# snesslot.net
KiCad netlist of a schematic drawn in Altium Designer
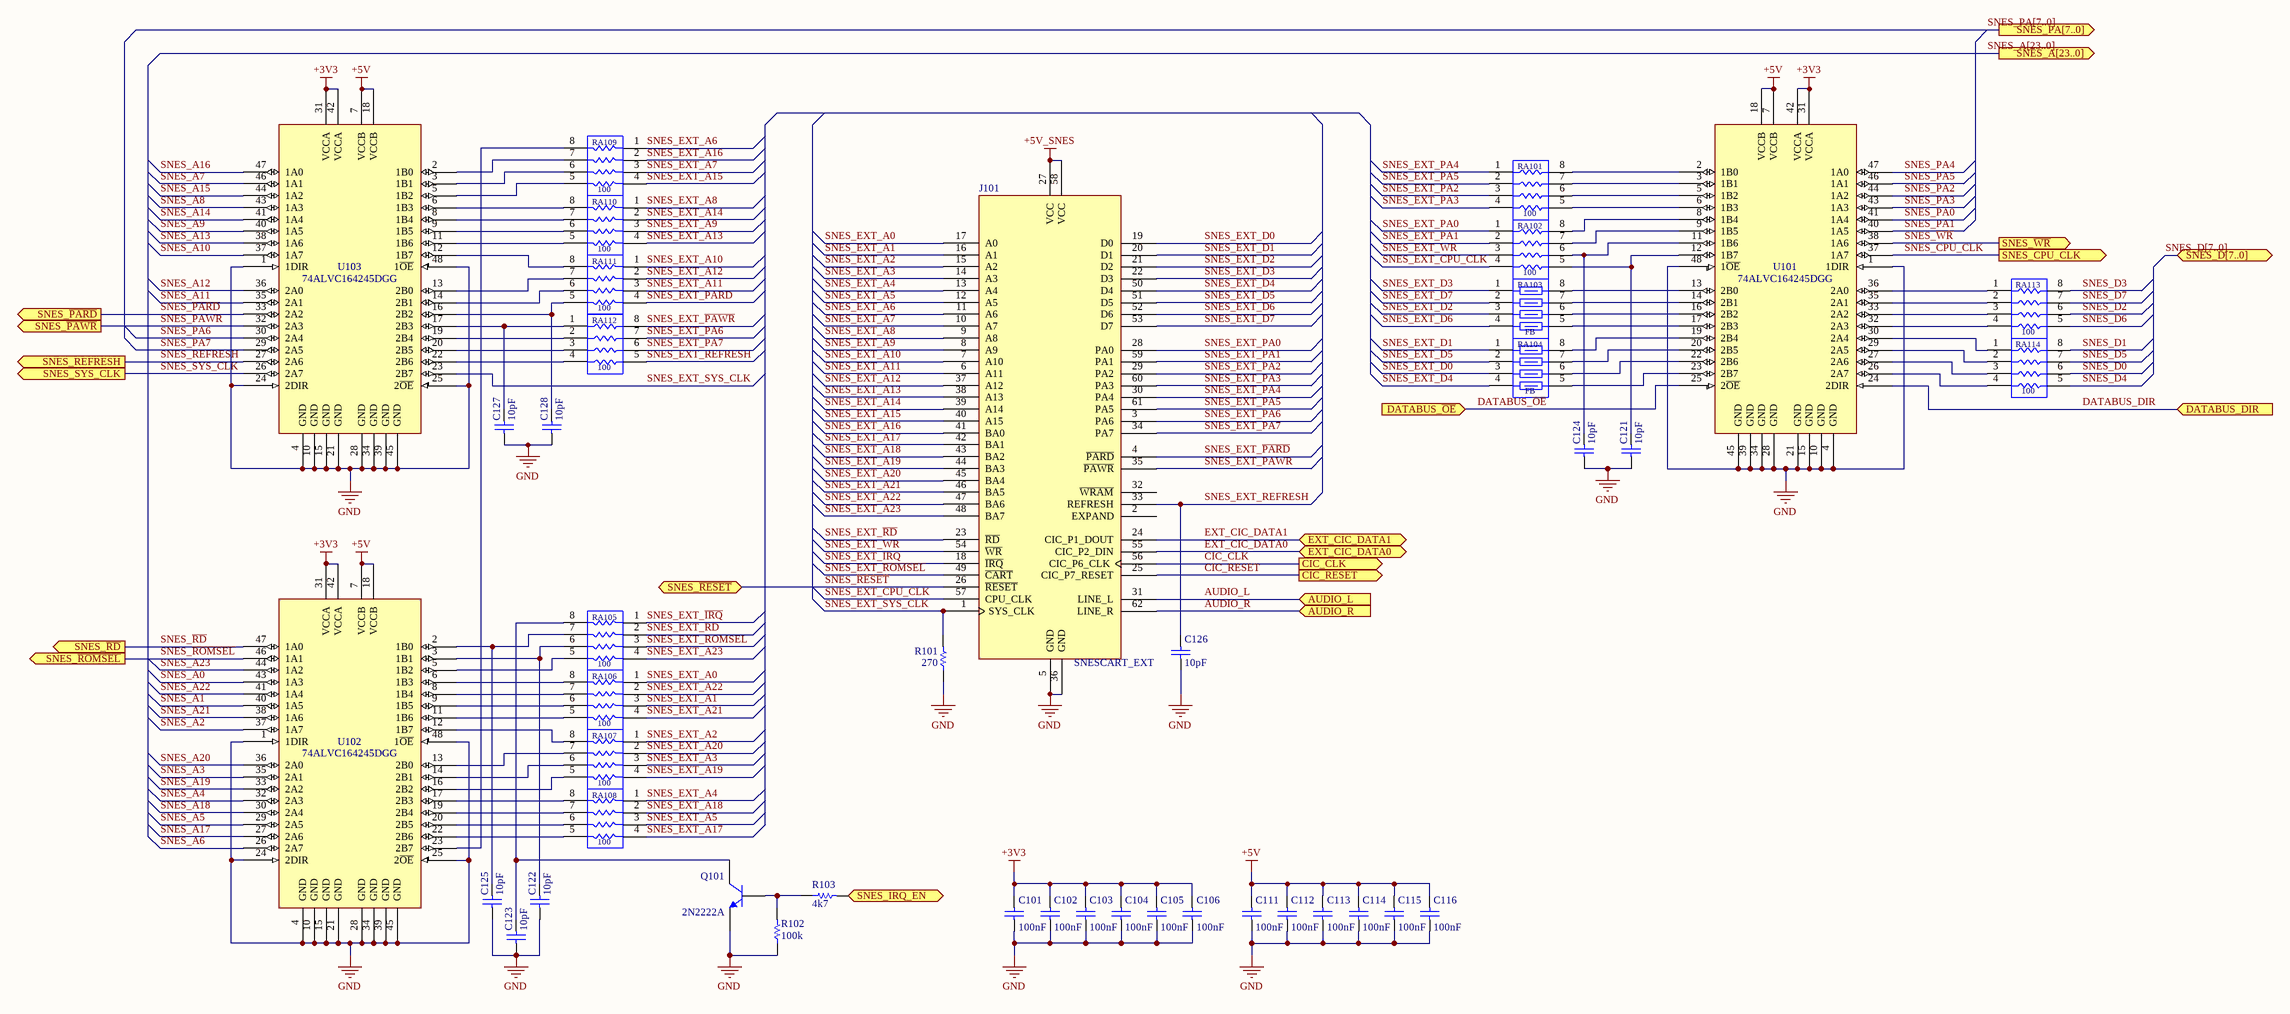
[diagram p0: snesslot.SchDoc]

(export (version "E")
  (design (tool "Eeschema 10.0.6"))
  (components
    (comp (ref "C101")
      (value "100nF")
      (footprint "SM0805")
      (description "Capacitor")
      (libsource (lib "Miscellaneous Devices") (part "Cap"))
    )
    (comp (ref "C102")
      (value "100nF")
      (footprint "SM0805")
      (description "Capacitor")
      (libsource (lib "Miscellaneous Devices") (part "Cap"))
    )
    (comp (ref "C103")
      (value "100nF")
      (footprint "SM0805")
      (description "Capacitor")
      (libsource (lib "Miscellaneous Devices") (part "Cap"))
    )
    (comp (ref "C104")
      (value "100nF")
      (footprint "SM0805")
      (description "Capacitor")
      (libsource (lib "Miscellaneous Devices") (part "Cap"))
    )
    (comp (ref "C105")
      (value "100nF")
      (footprint "SM0805")
      (description "Capacitor")
      (libsource (lib "Miscellaneous Devices") (part "Cap"))
    )
    (comp (ref "C106")
      (value "100nF")
      (footprint "SM0805")
      (description "Capacitor")
      (libsource (lib "Miscellaneous Devices") (part "Cap"))
    )
    (comp (ref "C111")
      (value "100nF")
      (footprint "SM0805")
      (description "Capacitor")
      (libsource (lib "Miscellaneous Devices") (part "Cap"))
    )
    (comp (ref "C112")
      (value "100nF")
      (footprint "SM0805")
      (description "Capacitor")
      (libsource (lib "Miscellaneous Devices") (part "Cap"))
    )
    (comp (ref "C113")
      (value "100nF")
      (footprint "SM0805")
      (description "Capacitor")
      (libsource (lib "Miscellaneous Devices") (part "Cap"))
    )
    (comp (ref "C114")
      (value "100nF")
      (footprint "SM0805")
      (description "Capacitor")
      (libsource (lib "Miscellaneous Devices") (part "Cap"))
    )
    (comp (ref "C115")
      (value "100nF")
      (footprint "SM0805")
      (description "Capacitor")
      (libsource (lib "Miscellaneous Devices") (part "Cap"))
    )
    (comp (ref "C116")
      (value "100nF")
      (footprint "SM0805")
      (description "Capacitor")
      (libsource (lib "Miscellaneous Devices") (part "Cap"))
    )
    (comp (ref "C121")
      (value "10pF")
      (footprint "SM0805")
      (description "Capacitor")
      (libsource (lib "Miscellaneous Devices") (part "Cap"))
    )
    (comp (ref "C122")
      (value "10pF")
      (footprint "SM0805")
      (description "Capacitor")
      (libsource (lib "Miscellaneous Devices") (part "Cap"))
    )
    (comp (ref "C123")
      (value "10pF")
      (footprint "SM0805")
      (description "Capacitor")
      (libsource (lib "Miscellaneous Devices") (part "Cap"))
    )
    (comp (ref "C124")
      (value "10pF")
      (footprint "SM0805")
      (description "Capacitor")
      (libsource (lib "Miscellaneous Devices") (part "Cap"))
    )
    (comp (ref "C125")
      (value "10pF")
      (footprint "SM0805")
      (description "Capacitor")
      (libsource (lib "Miscellaneous Devices") (part "Cap"))
    )
    (comp (ref "C126")
      (value "10pF")
      (footprint "SM0805")
      (description "Capacitor")
      (libsource (lib "Miscellaneous Devices") (part "Cap"))
    )
    (comp (ref "C127")
      (value "10pF")
      (footprint "SM0805")
      (description "Capacitor")
      (libsource (lib "Miscellaneous Devices") (part "Cap"))
    )
    (comp (ref "C128")
      (value "10pF")
      (footprint "SM0805")
      (description "Capacitor")
      (libsource (lib "Miscellaneous Devices") (part "Cap"))
    )
    (comp (ref "J101")
      (value "SNESCART_EXT")
      (footprint "SNESCART_EDGE_CONN")
      (libsource (lib "Schlib1") (part "SNESCART_EXT"))
    )
    (comp (ref "Q101")
      (value "2N2222A")
      (footprint "SOT23EBC")
      (description "NPN Transistor")
      (libsource (lib "Schlib1") (part "NPN"))
    )
    (comp (ref "R101")
      (value "270")
      (footprint "SM0805")
      (description "Resistor")
      (libsource (lib "Miscellaneous Devices") (part "Res1"))
    )
    (comp (ref "R102")
      (value "100k")
      (footprint "SM0805")
      (description "Resistor")
      (libsource (lib "Miscellaneous Devices") (part "Res1"))
    )
    (comp (ref "R103")
      (value "4k7")
      (footprint "SM0805")
      (description "Resistor")
      (libsource (lib "Miscellaneous Devices") (part "Res1"))
    )
    (comp (ref "RA101")
      (value "100")
      (footprint "R_PACK_1206_2")
      (description "Four Resistor Array")
      (libsource (lib "Schlib1") (part "R_PACK4"))
    )
    (comp (ref "RA102")
      (value "100")
      (footprint "R_PACK_1206_2")
      (description "Four Resistor Array")
      (libsource (lib "Schlib1") (part "R_PACK4"))
    )
    (comp (ref "RA103")
      (value "FB")
      (footprint "R_PACK_1206_2")
      (description "Four Ferrite Bead Array")
      (libsource (lib "Schlib1") (part "FB_PACK4"))
    )
    (comp (ref "RA104")
      (value "FB")
      (footprint "R_PACK_1206_2")
      (description "Four Ferrite Bead Array")
      (libsource (lib "Schlib1") (part "FB_PACK4"))
    )
    (comp (ref "RA105")
      (value "100")
      (footprint "R_PACK_1206_2")
      (description "Four Resistor Array")
      (libsource (lib "Schlib1") (part "R_PACK4"))
    )
    (comp (ref "RA106")
      (value "100")
      (footprint "R_PACK_1206_2")
      (description "Four Resistor Array")
      (libsource (lib "Schlib1") (part "R_PACK4"))
    )
    (comp (ref "RA107")
      (value "100")
      (footprint "R_PACK_1206_2")
      (description "Four Resistor Array")
      (libsource (lib "Schlib1") (part "R_PACK4"))
    )
    (comp (ref "RA108")
      (value "100")
      (footprint "R_PACK_1206_2")
      (description "Four Resistor Array")
      (libsource (lib "Schlib1") (part "R_PACK4"))
    )
    (comp (ref "RA109")
      (value "100")
      (footprint "R_PACK_1206_2")
      (description "Four Resistor Array")
      (libsource (lib "Schlib1") (part "R_PACK4"))
    )
    (comp (ref "RA110")
      (value "100")
      (footprint "R_PACK_1206_2")
      (description "Four Resistor Array")
      (libsource (lib "Schlib1") (part "R_PACK4"))
    )
    (comp (ref "RA111")
      (value "100")
      (footprint "R_PACK_1206_2")
      (description "Four Resistor Array")
      (libsource (lib "Schlib1") (part "R_PACK4"))
    )
    (comp (ref "RA112")
      (value "100")
      (footprint "R_PACK_1206_2")
      (description "Four Resistor Array")
      (libsource (lib "Schlib1") (part "R_PACK4"))
    )
    (comp (ref "RA113")
      (value "100")
      (footprint "R_PACK_1206_2")
      (description "Four Resistor Array")
      (libsource (lib "Schlib1") (part "R_PACK4"))
    )
    (comp (ref "RA114")
      (value "100")
      (footprint "R_PACK_1206_2")
      (description "Four Resistor Array")
      (libsource (lib "Schlib1") (part "R_PACK4"))
    )
    (comp (ref "U101")
      (value "74ALVC164245DGG")
      (footprint "TSSOP48")
      (libsource (lib "") (part "74ALVC164245_1"))
    )
    (comp (ref "U102")
      (value "74ALVC164245DGG")
      (footprint "TSSOP48")
      (libsource (lib "Schlib1") (part "74ALVC164245"))
    )
    (comp (ref "U103")
      (value "74ALVC164245DGG")
      (footprint "TSSOP48")
      (libsource (lib "Schlib1") (part "74ALVC164245"))
    )
  )
  (nets
    (net (code "1") (name "+3V3") (class "Default")
      (node (ref "C101") (pin "2") (pinfunction "2_2") (pintype "passive"))
      (node (ref "C102") (pin "2") (pinfunction "2_2") (pintype "passive"))
      (node (ref "C103") (pin "2") (pinfunction "2_2") (pintype "passive"))
      (node (ref "C104") (pin "2") (pinfunction "2_2") (pintype "passive"))
      (node (ref "C105") (pin "2") (pinfunction "2_2") (pintype "passive"))
      (node (ref "C106") (pin "2") (pinfunction "2_2") (pintype "passive"))
      (node (ref "U101") (pin "31") (pinfunction "VCCA_31") (pintype "power_in"))
      (node (ref "U101") (pin "42") (pinfunction "VCCA_42") (pintype "power_in"))
      (node (ref "U102") (pin "31") (pinfunction "VCCA_31") (pintype "power_in"))
      (node (ref "U102") (pin "42") (pinfunction "VCCA_42") (pintype "power_in"))
      (node (ref "U103") (pin "31") (pinfunction "VCCA_31") (pintype "power_in"))
      (node (ref "U103") (pin "42") (pinfunction "VCCA_42") (pintype "power_in"))
    )
    (net (code "2") (name "+5V") (class "Default")
      (node (ref "C111") (pin "2") (pinfunction "2_2") (pintype "passive"))
      (node (ref "C112") (pin "2") (pinfunction "2_2") (pintype "passive"))
      (node (ref "C113") (pin "2") (pinfunction "2_2") (pintype "passive"))
      (node (ref "C114") (pin "2") (pinfunction "2_2") (pintype "passive"))
      (node (ref "C115") (pin "2") (pinfunction "2_2") (pintype "passive"))
      (node (ref "C116") (pin "2") (pinfunction "2_2") (pintype "passive"))
      (node (ref "U101") (pin "18") (pinfunction "VCCB_18") (pintype "power_in"))
      (node (ref "U101") (pin "7") (pinfunction "VCCB_7") (pintype "power_in"))
      (node (ref "U102") (pin "18") (pinfunction "VCCB_18") (pintype "power_in"))
      (node (ref "U102") (pin "7") (pinfunction "VCCB_7") (pintype "power_in"))
      (node (ref "U103") (pin "18") (pinfunction "VCCB_18") (pintype "power_in"))
      (node (ref "U103") (pin "7") (pinfunction "VCCB_7") (pintype "power_in"))
    )
    (net (code "3") (name "+5V_SNES") (class "Default")
      (node (ref "J101") (pin "27") (pinfunction "VCC_27") (pintype "passive"))
      (node (ref "J101") (pin "58") (pinfunction "VCC_58") (pintype "passive"))
    )
    (net (code "4") (name "/AUDIO_L") (class "Default")
      (node (ref "J101") (pin "31") (pinfunction "LINE_L_31") (pintype "passive"))
    )
    (net (code "5") (name "/AUDIO_R") (class "Default")
      (node (ref "J101") (pin "62") (pinfunction "LINE_R_62") (pintype "passive"))
    )
    (net (code "6") (name "/CIC_CLK") (class "Default")
      (node (ref "J101") (pin "56") (pinfunction "CIC_P6_CLK_56") (pintype "passive"))
    )
    (net (code "7") (name "/CIC_RESET") (class "Default")
      (node (ref "J101") (pin "25") (pinfunction "CIC_P7_RESET_25") (pintype "passive"))
    )
    (net (code "8") (name "/DATABUS_DIR") (class "Default")
      (node (ref "U101") (pin "24") (pinfunction "2DIR_24") (pintype "input"))
    )
    (net (code "9") (name "/DATABUS_~{OE}") (class "Default")
      (node (ref "U101") (pin "25") (pinfunction "2~{OE}_25") (pintype "input"))
    )
    (net (code "10") (name "/EXT_CIC_DATA0") (class "Default")
      (node (ref "J101") (pin "55") (pinfunction "CIC_P2_DIN_55") (pintype "passive"))
    )
    (net (code "11") (name "/EXT_CIC_DATA1") (class "Default")
      (node (ref "J101") (pin "24") (pinfunction "CIC_P1_DOUT_24") (pintype "passive"))
    )
    (net (code "12") (name "/SNES_A0") (class "Default")
      (node (ref "U102") (pin "43") (pinfunction "1A3_43") (pintype "bidirectional"))
    )
    (net (code "13") (name "/SNES_A1") (class "Default")
      (node (ref "U102") (pin "40") (pinfunction "1A5_40") (pintype "bidirectional"))
    )
    (net (code "14") (name "/SNES_A2") (class "Default")
      (node (ref "U102") (pin "37") (pinfunction "1A7_37") (pintype "bidirectional"))
    )
    (net (code "15") (name "/SNES_A3") (class "Default")
      (node (ref "U102") (pin "35") (pinfunction "2A1_35") (pintype "bidirectional"))
    )
    (net (code "16") (name "/SNES_A4") (class "Default")
      (node (ref "U102") (pin "32") (pinfunction "2A3_32") (pintype "bidirectional"))
    )
    (net (code "17") (name "/SNES_A5") (class "Default")
      (node (ref "U102") (pin "29") (pinfunction "2A5_29") (pintype "bidirectional"))
    )
    (net (code "18") (name "/SNES_A6") (class "Default")
      (node (ref "U102") (pin "26") (pinfunction "2A7_26") (pintype "bidirectional"))
    )
    (net (code "19") (name "/SNES_A7") (class "Default")
      (node (ref "U103") (pin "46") (pinfunction "1A1_46") (pintype "bidirectional"))
    )
    (net (code "20") (name "/SNES_A8") (class "Default")
      (node (ref "U103") (pin "43") (pinfunction "1A3_43") (pintype "bidirectional"))
    )
    (net (code "21") (name "/SNES_A9") (class "Default")
      (node (ref "U103") (pin "40") (pinfunction "1A5_40") (pintype "bidirectional"))
    )
    (net (code "22") (name "/SNES_A10") (class "Default")
      (node (ref "U103") (pin "37") (pinfunction "1A7_37") (pintype "bidirectional"))
    )
    (net (code "23") (name "/SNES_A11") (class "Default")
      (node (ref "U103") (pin "35") (pinfunction "2A1_35") (pintype "bidirectional"))
    )
    (net (code "24") (name "/SNES_A12") (class "Default")
      (node (ref "U103") (pin "36") (pinfunction "2A0_36") (pintype "bidirectional"))
    )
    (net (code "25") (name "/SNES_A13") (class "Default")
      (node (ref "U103") (pin "38") (pinfunction "1A6_38") (pintype "bidirectional"))
    )
    (net (code "26") (name "/SNES_A14") (class "Default")
      (node (ref "U103") (pin "41") (pinfunction "1A4_41") (pintype "bidirectional"))
    )
    (net (code "27") (name "/SNES_A15") (class "Default")
      (node (ref "U103") (pin "44") (pinfunction "1A2_44") (pintype "bidirectional"))
    )
    (net (code "28") (name "/SNES_A16") (class "Default")
      (node (ref "U103") (pin "47") (pinfunction "1A0_47") (pintype "bidirectional"))
    )
    (net (code "29") (name "/SNES_A17") (class "Default")
      (node (ref "U102") (pin "27") (pinfunction "2A6_27") (pintype "bidirectional"))
    )
    (net (code "30") (name "/SNES_A18") (class "Default")
      (node (ref "U102") (pin "30") (pinfunction "2A4_30") (pintype "bidirectional"))
    )
    (net (code "31") (name "/SNES_A19") (class "Default")
      (node (ref "U102") (pin "33") (pinfunction "2A2_33") (pintype "bidirectional"))
    )
    (net (code "32") (name "/SNES_A20") (class "Default")
      (node (ref "U102") (pin "36") (pinfunction "2A0_36") (pintype "bidirectional"))
    )
    (net (code "33") (name "/SNES_A21") (class "Default")
      (node (ref "U102") (pin "38") (pinfunction "1A6_38") (pintype "bidirectional"))
    )
    (net (code "34") (name "/SNES_A22") (class "Default")
      (node (ref "U102") (pin "41") (pinfunction "1A4_41") (pintype "bidirectional"))
    )
    (net (code "35") (name "/SNES_A23") (class "Default")
      (node (ref "U102") (pin "44") (pinfunction "1A2_44") (pintype "bidirectional"))
    )
    (net (code "37") (name "/SNES_CPU_CLK") (class "Default")
      (node (ref "U101") (pin "37") (pinfunction "1A7_37") (pintype "bidirectional"))
    )
    (net (code "38") (name "/SNES_D0") (class "Default")
      (node (ref "RA114") (pin "6") (pinfunction "6_6") (pintype "passive"))
    )
    (net (code "39") (name "/SNES_D1") (class "Default")
      (node (ref "RA114") (pin "8") (pinfunction "8_8") (pintype "passive"))
    )
    (net (code "40") (name "/SNES_D2") (class "Default")
      (node (ref "RA113") (pin "6") (pinfunction "6_6") (pintype "passive"))
    )
    (net (code "41") (name "/SNES_D3") (class "Default")
      (node (ref "RA113") (pin "8") (pinfunction "8_8") (pintype "passive"))
    )
    (net (code "42") (name "/SNES_D4") (class "Default")
      (node (ref "RA114") (pin "5") (pinfunction "5_5") (pintype "passive"))
    )
    (net (code "43") (name "/SNES_D5") (class "Default")
      (node (ref "RA114") (pin "7") (pinfunction "7_7") (pintype "passive"))
    )
    (net (code "44") (name "/SNES_D6") (class "Default")
      (node (ref "RA113") (pin "5") (pinfunction "5_5") (pintype "passive"))
    )
    (net (code "45") (name "/SNES_D7") (class "Default")
      (node (ref "RA113") (pin "7") (pinfunction "7_7") (pintype "passive"))
    )
    (net (code "47") (name "/SNES_EXT_A0") (class "Default")
      (node (ref "J101") (pin "17") (pinfunction "A0_17") (pintype "passive"))
      (node (ref "RA106") (pin "1") (pinfunction "1_1") (pintype "passive"))
    )
    (net (code "48") (name "/SNES_EXT_A1") (class "Default")
      (node (ref "J101") (pin "16") (pinfunction "A1_16") (pintype "passive"))
      (node (ref "RA106") (pin "3") (pinfunction "3_3") (pintype "passive"))
    )
    (net (code "49") (name "/SNES_EXT_A2") (class "Default")
      (node (ref "J101") (pin "15") (pinfunction "A2_15") (pintype "passive"))
      (node (ref "RA107") (pin "1") (pinfunction "1_1") (pintype "passive"))
    )
    (net (code "50") (name "/SNES_EXT_A3") (class "Default")
      (node (ref "J101") (pin "14") (pinfunction "A3_14") (pintype "passive"))
      (node (ref "RA107") (pin "3") (pinfunction "3_3") (pintype "passive"))
    )
    (net (code "51") (name "/SNES_EXT_A4") (class "Default")
      (node (ref "J101") (pin "13") (pinfunction "A4_13") (pintype "passive"))
      (node (ref "RA108") (pin "1") (pinfunction "1_1") (pintype "passive"))
    )
    (net (code "52") (name "/SNES_EXT_A5") (class "Default")
      (node (ref "J101") (pin "12") (pinfunction "A5_12") (pintype "passive"))
      (node (ref "RA108") (pin "3") (pinfunction "3_3") (pintype "passive"))
    )
    (net (code "53") (name "/SNES_EXT_A6") (class "Default")
      (node (ref "J101") (pin "11") (pinfunction "A6_11") (pintype "passive"))
      (node (ref "RA109") (pin "1") (pinfunction "1_1") (pintype "passive"))
    )
    (net (code "54") (name "/SNES_EXT_A7") (class "Default")
      (node (ref "J101") (pin "10") (pinfunction "A7_10") (pintype "passive"))
      (node (ref "RA109") (pin "3") (pinfunction "3_3") (pintype "passive"))
    )
    (net (code "55") (name "/SNES_EXT_A8") (class "Default")
      (node (ref "J101") (pin "9") (pinfunction "A8_9") (pintype "passive"))
      (node (ref "RA110") (pin "1") (pinfunction "1_1") (pintype "passive"))
    )
    (net (code "56") (name "/SNES_EXT_A9") (class "Default")
      (node (ref "J101") (pin "8") (pinfunction "A9_8") (pintype "passive"))
      (node (ref "RA110") (pin "3") (pinfunction "3_3") (pintype "passive"))
    )
    (net (code "57") (name "/SNES_EXT_A10") (class "Default")
      (node (ref "J101") (pin "7") (pinfunction "A10_7") (pintype "passive"))
      (node (ref "RA111") (pin "1") (pinfunction "1_1") (pintype "passive"))
    )
    (net (code "58") (name "/SNES_EXT_A11") (class "Default")
      (node (ref "J101") (pin "6") (pinfunction "A11_6") (pintype "passive"))
      (node (ref "RA111") (pin "3") (pinfunction "3_3") (pintype "passive"))
    )
    (net (code "59") (name "/SNES_EXT_A12") (class "Default")
      (node (ref "J101") (pin "37") (pinfunction "A12_37") (pintype "passive"))
      (node (ref "RA111") (pin "2") (pinfunction "2_2") (pintype "passive"))
    )
    (net (code "60") (name "/SNES_EXT_A13") (class "Default")
      (node (ref "J101") (pin "38") (pinfunction "A13_38") (pintype "passive"))
      (node (ref "RA110") (pin "4") (pinfunction "4_4") (pintype "passive"))
    )
    (net (code "61") (name "/SNES_EXT_A14") (class "Default")
      (node (ref "J101") (pin "39") (pinfunction "A14_39") (pintype "passive"))
      (node (ref "RA110") (pin "2") (pinfunction "2_2") (pintype "passive"))
    )
    (net (code "62") (name "/SNES_EXT_A15") (class "Default")
      (node (ref "J101") (pin "40") (pinfunction "A15_40") (pintype "passive"))
      (node (ref "RA109") (pin "4") (pinfunction "4_4") (pintype "passive"))
    )
    (net (code "63") (name "/SNES_EXT_A16") (class "Default")
      (node (ref "J101") (pin "41") (pinfunction "BA0_41") (pintype "passive"))
      (node (ref "RA109") (pin "2") (pinfunction "2_2") (pintype "passive"))
    )
    (net (code "64") (name "/SNES_EXT_A17") (class "Default")
      (node (ref "J101") (pin "42") (pinfunction "BA1_42") (pintype "passive"))
      (node (ref "RA108") (pin "4") (pinfunction "4_4") (pintype "passive"))
    )
    (net (code "65") (name "/SNES_EXT_A18") (class "Default")
      (node (ref "J101") (pin "43") (pinfunction "BA2_43") (pintype "passive"))
      (node (ref "RA108") (pin "2") (pinfunction "2_2") (pintype "passive"))
    )
    (net (code "66") (name "/SNES_EXT_A19") (class "Default")
      (node (ref "J101") (pin "44") (pinfunction "BA3_44") (pintype "passive"))
      (node (ref "RA107") (pin "4") (pinfunction "4_4") (pintype "passive"))
    )
    (net (code "67") (name "/SNES_EXT_A20") (class "Default")
      (node (ref "J101") (pin "45") (pinfunction "BA4_45") (pintype "passive"))
      (node (ref "RA107") (pin "2") (pinfunction "2_2") (pintype "passive"))
    )
    (net (code "68") (name "/SNES_EXT_A21") (class "Default")
      (node (ref "J101") (pin "46") (pinfunction "BA5_46") (pintype "passive"))
      (node (ref "RA106") (pin "4") (pinfunction "4_4") (pintype "passive"))
    )
    (net (code "69") (name "/SNES_EXT_A22") (class "Default")
      (node (ref "J101") (pin "47") (pinfunction "BA6_47") (pintype "passive"))
      (node (ref "RA106") (pin "2") (pinfunction "2_2") (pintype "passive"))
    )
    (net (code "70") (name "/SNES_EXT_A23") (class "Default")
      (node (ref "J101") (pin "48") (pinfunction "BA7_48") (pintype "passive"))
      (node (ref "RA105") (pin "4") (pinfunction "4_4") (pintype "passive"))
    )
    (net (code "71") (name "/SNES_EXT_CPU_CLK") (class "Default")
      (node (ref "J101") (pin "57") (pinfunction "CPU_CLK_57") (pintype "passive"))
      (node (ref "RA102") (pin "4") (pinfunction "4_4") (pintype "passive"))
    )
    (net (code "72") (name "/SNES_EXT_D0") (class "Default")
      (node (ref "J101") (pin "19") (pinfunction "D0_19") (pintype "passive"))
      (node (ref "RA104") (pin "3") (pinfunction "3_3") (pintype "passive"))
    )
    (net (code "73") (name "/SNES_EXT_D1") (class "Default")
      (node (ref "J101") (pin "20") (pinfunction "D1_20") (pintype "passive"))
      (node (ref "RA104") (pin "1") (pinfunction "1_1") (pintype "passive"))
    )
    (net (code "74") (name "/SNES_EXT_D2") (class "Default")
      (node (ref "J101") (pin "21") (pinfunction "D2_21") (pintype "passive"))
      (node (ref "RA103") (pin "3") (pinfunction "3_3") (pintype "passive"))
    )
    (net (code "75") (name "/SNES_EXT_D3") (class "Default")
      (node (ref "J101") (pin "22") (pinfunction "D3_22") (pintype "passive"))
      (node (ref "RA103") (pin "1") (pinfunction "1_1") (pintype "passive"))
    )
    (net (code "76") (name "/SNES_EXT_D4") (class "Default")
      (node (ref "J101") (pin "50") (pinfunction "D4_50") (pintype "passive"))
      (node (ref "RA104") (pin "4") (pinfunction "4_4") (pintype "passive"))
    )
    (net (code "77") (name "/SNES_EXT_D5") (class "Default")
      (node (ref "J101") (pin "51") (pinfunction "D5_51") (pintype "passive"))
      (node (ref "RA104") (pin "2") (pinfunction "2_2") (pintype "passive"))
    )
    (net (code "78") (name "/SNES_EXT_D6") (class "Default")
      (node (ref "J101") (pin "52") (pinfunction "D6_52") (pintype "passive"))
      (node (ref "RA103") (pin "4") (pinfunction "4_4") (pintype "passive"))
    )
    (net (code "79") (name "/SNES_EXT_D7") (class "Default")
      (node (ref "J101") (pin "53") (pinfunction "D7_53") (pintype "passive"))
      (node (ref "RA103") (pin "2") (pinfunction "2_2") (pintype "passive"))
    )
    (net (code "80") (name "/SNES_EXT_PA0") (class "Default")
      (node (ref "J101") (pin "28") (pinfunction "PA0_28") (pintype "passive"))
      (node (ref "RA102") (pin "1") (pinfunction "1_1") (pintype "passive"))
    )
    (net (code "81") (name "/SNES_EXT_PA1") (class "Default")
      (node (ref "J101") (pin "59") (pinfunction "PA1_59") (pintype "passive"))
      (node (ref "RA102") (pin "2") (pinfunction "2_2") (pintype "passive"))
    )
    (net (code "82") (name "/SNES_EXT_PA2") (class "Default")
      (node (ref "J101") (pin "29") (pinfunction "PA2_29") (pintype "passive"))
      (node (ref "RA101") (pin "3") (pinfunction "3_3") (pintype "passive"))
    )
    (net (code "83") (name "/SNES_EXT_PA3") (class "Default")
      (node (ref "J101") (pin "60") (pinfunction "PA3_60") (pintype "passive"))
      (node (ref "RA101") (pin "4") (pinfunction "4_4") (pintype "passive"))
    )
    (net (code "84") (name "/SNES_EXT_PA4") (class "Default")
      (node (ref "J101") (pin "30") (pinfunction "PA4_30") (pintype "passive"))
      (node (ref "RA101") (pin "1") (pinfunction "1_1") (pintype "passive"))
    )
    (net (code "85") (name "/SNES_EXT_PA5") (class "Default")
      (node (ref "J101") (pin "61") (pinfunction "PA5_61") (pintype "passive"))
      (node (ref "RA101") (pin "2") (pinfunction "2_2") (pintype "passive"))
    )
    (net (code "86") (name "/SNES_EXT_PA6") (class "Default")
      (node (ref "J101") (pin "3") (pinfunction "PA6_3") (pintype "passive"))
      (node (ref "RA112") (pin "7") (pinfunction "7_7") (pintype "passive"))
    )
    (net (code "87") (name "/SNES_EXT_PA7") (class "Default")
      (node (ref "J101") (pin "34") (pinfunction "PA7_34") (pintype "passive"))
      (node (ref "RA112") (pin "6") (pinfunction "6_6") (pintype "passive"))
    )
    (net (code "88") (name "/SNES_EXT_REFRESH") (class "Default")
      (node (ref "C126") (pin "1") (pinfunction "1_1") (pintype "passive"))
      (node (ref "J101") (pin "33") (pinfunction "REFRESH_33") (pintype "passive"))
      (node (ref "RA112") (pin "5") (pinfunction "5_5") (pintype "passive"))
    )
    (net (code "89") (name "/SNES_EXT_SYS_CLK") (class "Default")
      (node (ref "J101") (pin "1") (pinfunction "SYS_CLK_1") (pintype "passive"))
      (node (ref "R101") (pin "2") (pinfunction "2_2") (pintype "passive"))
      (node (ref "U103") (pin "23") (pinfunction "2B7_23") (pintype "bidirectional"))
    )
    (net (code "90") (name "/SNES_EXT_~{IRQ}") (class "Default")
      (node (ref "J101") (pin "18") (pinfunction "~{IRQ}_18") (pintype "passive"))
      (node (ref "RA105") (pin "1") (pinfunction "1_1") (pintype "passive"))
    )
    (net (code "91") (name "/SNES_EXT_~{PARD}") (class "Default")
      (node (ref "J101") (pin "4") (pinfunction "~{PARD}_4") (pintype "passive"))
      (node (ref "RA111") (pin "4") (pinfunction "4_4") (pintype "passive"))
    )
    (net (code "92") (name "/SNES_EXT_~{PAWR}") (class "Default")
      (node (ref "J101") (pin "35") (pinfunction "~{PAWR}_35") (pintype "passive"))
      (node (ref "RA112") (pin "8") (pinfunction "8_8") (pintype "passive"))
    )
    (net (code "93") (name "/SNES_EXT_~{RD}") (class "Default")
      (node (ref "J101") (pin "23") (pinfunction "~{RD}_23") (pintype "passive"))
      (node (ref "RA105") (pin "2") (pinfunction "2_2") (pintype "passive"))
    )
    (net (code "94") (name "/SNES_EXT_~{ROMSEL}") (class "Default")
      (node (ref "J101") (pin "49") (pinfunction "~{CART}_49") (pintype "passive"))
      (node (ref "RA105") (pin "3") (pinfunction "3_3") (pintype "passive"))
    )
    (net (code "95") (name "/SNES_EXT_~{WR}") (class "Default")
      (node (ref "J101") (pin "54") (pinfunction "~{WR}_54") (pintype "passive"))
      (node (ref "RA102") (pin "3") (pinfunction "3_3") (pintype "passive"))
    )
    (net (code "96") (name "/SNES_IRQ_EN") (class "Default")
      (node (ref "R103") (pin "2") (pinfunction "2_2") (pintype "passive"))
    )
    (net (code "97") (name "/SNES_PA0") (class "Default")
      (node (ref "U101") (pin "41") (pinfunction "1A4_41") (pintype "bidirectional"))
    )
    (net (code "98") (name "/SNES_PA1") (class "Default")
      (node (ref "U101") (pin "40") (pinfunction "1A5_40") (pintype "bidirectional"))
    )
    (net (code "99") (name "/SNES_PA2") (class "Default")
      (node (ref "U101") (pin "44") (pinfunction "1A2_44") (pintype "bidirectional"))
    )
    (net (code "100") (name "/SNES_PA3") (class "Default")
      (node (ref "U101") (pin "43") (pinfunction "1A3_43") (pintype "bidirectional"))
    )
    (net (code "101") (name "/SNES_PA4") (class "Default")
      (node (ref "U101") (pin "47") (pinfunction "1A0_47") (pintype "bidirectional"))
    )
    (net (code "102") (name "/SNES_PA5") (class "Default")
      (node (ref "U101") (pin "46") (pinfunction "1A1_46") (pintype "bidirectional"))
    )
    (net (code "103") (name "/SNES_PA6") (class "Default")
      (node (ref "U103") (pin "30") (pinfunction "2A4_30") (pintype "bidirectional"))
    )
    (net (code "104") (name "/SNES_PA7") (class "Default")
      (node (ref "U103") (pin "29") (pinfunction "2A5_29") (pintype "bidirectional"))
    )
    (net (code "106") (name "/SNES_REFRESH") (class "Default")
      (node (ref "U103") (pin "27") (pinfunction "2A6_27") (pintype "bidirectional"))
    )
    (net (code "107") (name "/SNES_SYS_CLK") (class "Default")
      (node (ref "U103") (pin "26") (pinfunction "2A7_26") (pintype "bidirectional"))
    )
    (net (code "108") (name "/SNES_~{PARD}") (class "Default")
      (node (ref "U103") (pin "33") (pinfunction "2A2_33") (pintype "bidirectional"))
    )
    (net (code "109") (name "/SNES_~{PAWR}") (class "Default")
      (node (ref "U103") (pin "32") (pinfunction "2A3_32") (pintype "bidirectional"))
    )
    (net (code "110") (name "/SNES_~{RD}") (class "Default")
      (node (ref "U102") (pin "47") (pinfunction "1A0_47") (pintype "bidirectional"))
    )
    (net (code "111") (name "/SNES_~{RESET}") (class "Default")
      (node (ref "J101") (pin "26") (pinfunction "~{RESET}_26") (pintype "passive"))
    )
    (net (code "112") (name "/SNES_~{ROMSEL}") (class "Default")
      (node (ref "U102") (pin "46") (pinfunction "1A1_46") (pintype "bidirectional"))
    )
    (net (code "113") (name "/SNES_~{WR}") (class "Default")
      (node (ref "U101") (pin "38") (pinfunction "1A6_38") (pintype "bidirectional"))
    )
    (net (code "114") (name "GND") (class "Default")
      (node (ref "C101") (pin "1") (pinfunction "1_1") (pintype "passive"))
      (node (ref "C102") (pin "1") (pinfunction "1_1") (pintype "passive"))
      (node (ref "C103") (pin "1") (pinfunction "1_1") (pintype "passive"))
      (node (ref "C104") (pin "1") (pinfunction "1_1") (pintype "passive"))
      (node (ref "C105") (pin "1") (pinfunction "1_1") (pintype "passive"))
      (node (ref "C106") (pin "1") (pinfunction "1_1") (pintype "passive"))
      (node (ref "C111") (pin "1") (pinfunction "1_1") (pintype "passive"))
      (node (ref "C112") (pin "1") (pinfunction "1_1") (pintype "passive"))
      (node (ref "C113") (pin "1") (pinfunction "1_1") (pintype "passive"))
      (node (ref "C114") (pin "1") (pinfunction "1_1") (pintype "passive"))
      (node (ref "C115") (pin "1") (pinfunction "1_1") (pintype "passive"))
      (node (ref "C116") (pin "1") (pinfunction "1_1") (pintype "passive"))
      (node (ref "C121") (pin "1") (pinfunction "1_1") (pintype "passive"))
      (node (ref "C122") (pin "1") (pinfunction "1_1") (pintype "passive"))
      (node (ref "C123") (pin "1") (pinfunction "1_1") (pintype "passive"))
      (node (ref "C124") (pin "1") (pinfunction "1_1") (pintype "passive"))
      (node (ref "C125") (pin "1") (pinfunction "1_1") (pintype "passive"))
      (node (ref "C126") (pin "2") (pinfunction "2_2") (pintype "passive"))
      (node (ref "C127") (pin "1") (pinfunction "1_1") (pintype "passive"))
      (node (ref "C128") (pin "1") (pinfunction "1_1") (pintype "passive"))
      (node (ref "J101") (pin "36") (pinfunction "GND_36") (pintype "passive"))
      (node (ref "J101") (pin "5") (pinfunction "GND_5") (pintype "passive"))
      (node (ref "Q101") (pin "2") (pinfunction "E_2") (pintype "passive"))
      (node (ref "R101") (pin "1") (pinfunction "1_1") (pintype "passive"))
      (node (ref "R102") (pin "1") (pinfunction "1_1") (pintype "passive"))
      (node (ref "U101") (pin "1") (pinfunction "1DIR_1") (pintype "input"))
      (node (ref "U101") (pin "10") (pinfunction "GND_10") (pintype "power_in"))
      (node (ref "U101") (pin "15") (pinfunction "GND_15") (pintype "power_in"))
      (node (ref "U101") (pin "21") (pinfunction "GND_21") (pintype "power_in"))
      (node (ref "U101") (pin "28") (pinfunction "GND_28") (pintype "power_in"))
      (node (ref "U101") (pin "34") (pinfunction "GND_34") (pintype "power_in"))
      (node (ref "U101") (pin "39") (pinfunction "GND_39") (pintype "power_in"))
      (node (ref "U101") (pin "4") (pinfunction "GND_4") (pintype "power_in"))
      (node (ref "U101") (pin "45") (pinfunction "GND_45") (pintype "power_in"))
      (node (ref "U101") (pin "48") (pinfunction "1~{OE}_48") (pintype "input"))
      (node (ref "U102") (pin "1") (pinfunction "1DIR_1") (pintype "input"))
      (node (ref "U102") (pin "10") (pinfunction "GND_10") (pintype "power_in"))
      (node (ref "U102") (pin "15") (pinfunction "GND_15") (pintype "power_in"))
      (node (ref "U102") (pin "21") (pinfunction "GND_21") (pintype "power_in"))
      (node (ref "U102") (pin "24") (pinfunction "2DIR_24") (pintype "input"))
      (node (ref "U102") (pin "25") (pinfunction "2~{OE}_25") (pintype "input"))
      (node (ref "U102") (pin "28") (pinfunction "GND_28") (pintype "power_in"))
      (node (ref "U102") (pin "34") (pinfunction "GND_34") (pintype "power_in"))
      (node (ref "U102") (pin "39") (pinfunction "GND_39") (pintype "power_in"))
      (node (ref "U102") (pin "4") (pinfunction "GND_4") (pintype "power_in"))
      (node (ref "U102") (pin "45") (pinfunction "GND_45") (pintype "power_in"))
      (node (ref "U102") (pin "48") (pinfunction "1~{OE}_48") (pintype "input"))
      (node (ref "U103") (pin "1") (pinfunction "1DIR_1") (pintype "input"))
      (node (ref "U103") (pin "10") (pinfunction "GND_10") (pintype "power_in"))
      (node (ref "U103") (pin "15") (pinfunction "GND_15") (pintype "power_in"))
      (node (ref "U103") (pin "21") (pinfunction "GND_21") (pintype "power_in"))
      (node (ref "U103") (pin "24") (pinfunction "2DIR_24") (pintype "input"))
      (node (ref "U103") (pin "25") (pinfunction "2~{OE}_25") (pintype "input"))
      (node (ref "U103") (pin "28") (pinfunction "GND_28") (pintype "power_in"))
      (node (ref "U103") (pin "34") (pinfunction "GND_34") (pintype "power_in"))
      (node (ref "U103") (pin "39") (pinfunction "GND_39") (pintype "power_in"))
      (node (ref "U103") (pin "4") (pinfunction "GND_4") (pintype "power_in"))
      (node (ref "U103") (pin "45") (pinfunction "GND_45") (pintype "power_in"))
      (node (ref "U103") (pin "48") (pinfunction "1~{OE}_48") (pintype "input"))
    )
    (net (code "115") (name "Net-(Q101-B)") (class "Default")
      (node (ref "Q101") (pin "1") (pinfunction "B_1") (pintype "passive"))
      (node (ref "R102") (pin "2") (pinfunction "2_2") (pintype "passive"))
      (node (ref "R103") (pin "1") (pinfunction "1_1") (pintype "passive"))
    )
    (net (code "116") (name "Net-(Q101-C)") (class "Default")
      (node (ref "C123") (pin "2") (pinfunction "2_2") (pintype "passive"))
      (node (ref "Q101") (pin "3") (pinfunction "C_3") (pintype "passive"))
      (node (ref "RA105") (pin "8") (pinfunction "8_8") (pintype "passive"))
    )
    (net (code "117") (name "Net-(U101-1B0)") (class "Default")
      (node (ref "RA101") (pin "8") (pinfunction "8_8") (pintype "passive"))
      (node (ref "U101") (pin "2") (pinfunction "1B0_2") (pintype "bidirectional"))
    )
    (net (code "118") (name "Net-(U101-1B1)") (class "Default")
      (node (ref "RA101") (pin "7") (pinfunction "7_7") (pintype "passive"))
      (node (ref "U101") (pin "3") (pinfunction "1B1_3") (pintype "bidirectional"))
    )
    (net (code "119") (name "Net-(U101-1B2)") (class "Default")
      (node (ref "RA101") (pin "6") (pinfunction "6_6") (pintype "passive"))
      (node (ref "U101") (pin "5") (pinfunction "1B2_5") (pintype "bidirectional"))
    )
    (net (code "120") (name "Net-(U101-1B3)") (class "Default")
      (node (ref "RA101") (pin "5") (pinfunction "5_5") (pintype "passive"))
      (node (ref "U101") (pin "6") (pinfunction "1B3_6") (pintype "bidirectional"))
    )
    (net (code "121") (name "Net-(U101-1B4)") (class "Default")
      (node (ref "RA102") (pin "8") (pinfunction "8_8") (pintype "passive"))
      (node (ref "U101") (pin "8") (pinfunction "1B4_8") (pintype "bidirectional"))
    )
    (net (code "122") (name "Net-(U101-1B5)") (class "Default")
      (node (ref "RA102") (pin "7") (pinfunction "7_7") (pintype "passive"))
      (node (ref "U101") (pin "9") (pinfunction "1B5_9") (pintype "bidirectional"))
    )
    (net (code "123") (name "Net-(U101-1B6)") (class "Default")
      (node (ref "C124") (pin "2") (pinfunction "2_2") (pintype "passive"))
      (node (ref "RA102") (pin "6") (pinfunction "6_6") (pintype "passive"))
      (node (ref "U101") (pin "11") (pinfunction "1B6_11") (pintype "bidirectional"))
    )
    (net (code "124") (name "Net-(U101-1B7)") (class "Default")
      (node (ref "C121") (pin "2") (pinfunction "2_2") (pintype "passive"))
      (node (ref "RA102") (pin "5") (pinfunction "5_5") (pintype "passive"))
      (node (ref "U101") (pin "12") (pinfunction "1B7_12") (pintype "bidirectional"))
    )
    (net (code "125") (name "Net-(U101-2A0)") (class "Default")
      (node (ref "RA113") (pin "1") (pinfunction "1_1") (pintype "passive"))
      (node (ref "U101") (pin "36") (pinfunction "2A0_36") (pintype "bidirectional"))
    )
    (net (code "126") (name "Net-(U101-2A1)") (class "Default")
      (node (ref "RA113") (pin "2") (pinfunction "2_2") (pintype "passive"))
      (node (ref "U101") (pin "35") (pinfunction "2A1_35") (pintype "bidirectional"))
    )
    (net (code "127") (name "Net-(U101-2A2)") (class "Default")
      (node (ref "RA113") (pin "3") (pinfunction "3_3") (pintype "passive"))
      (node (ref "U101") (pin "33") (pinfunction "2A2_33") (pintype "bidirectional"))
    )
    (net (code "128") (name "Net-(U101-2A3)") (class "Default")
      (node (ref "RA113") (pin "4") (pinfunction "4_4") (pintype "passive"))
      (node (ref "U101") (pin "32") (pinfunction "2A3_32") (pintype "bidirectional"))
    )
    (net (code "129") (name "Net-(U101-2A4)") (class "Default")
      (node (ref "RA114") (pin "1") (pinfunction "1_1") (pintype "passive"))
      (node (ref "U101") (pin "30") (pinfunction "2A4_30") (pintype "bidirectional"))
    )
    (net (code "130") (name "Net-(U101-2A5)") (class "Default")
      (node (ref "RA114") (pin "2") (pinfunction "2_2") (pintype "passive"))
      (node (ref "U101") (pin "29") (pinfunction "2A5_29") (pintype "bidirectional"))
    )
    (net (code "131") (name "Net-(U101-2A6)") (class "Default")
      (node (ref "RA114") (pin "3") (pinfunction "3_3") (pintype "passive"))
      (node (ref "U101") (pin "27") (pinfunction "2A6_27") (pintype "bidirectional"))
    )
    (net (code "132") (name "Net-(U101-2A7)") (class "Default")
      (node (ref "RA114") (pin "4") (pinfunction "4_4") (pintype "passive"))
      (node (ref "U101") (pin "26") (pinfunction "2A7_26") (pintype "bidirectional"))
    )
    (net (code "133") (name "Net-(U101-2B0)") (class "Default")
      (node (ref "RA103") (pin "8") (pinfunction "8_8") (pintype "passive"))
      (node (ref "U101") (pin "13") (pinfunction "2B0_13") (pintype "bidirectional"))
    )
    (net (code "134") (name "Net-(U101-2B1)") (class "Default")
      (node (ref "RA103") (pin "7") (pinfunction "7_7") (pintype "passive"))
      (node (ref "U101") (pin "14") (pinfunction "2B1_14") (pintype "bidirectional"))
    )
    (net (code "135") (name "Net-(U101-2B2)") (class "Default")
      (node (ref "RA103") (pin "6") (pinfunction "6_6") (pintype "passive"))
      (node (ref "U101") (pin "16") (pinfunction "2B2_16") (pintype "bidirectional"))
    )
    (net (code "136") (name "Net-(U101-2B3)") (class "Default")
      (node (ref "RA103") (pin "5") (pinfunction "5_5") (pintype "passive"))
      (node (ref "U101") (pin "17") (pinfunction "2B3_17") (pintype "bidirectional"))
    )
    (net (code "137") (name "Net-(U101-2B4)") (class "Default")
      (node (ref "RA104") (pin "8") (pinfunction "8_8") (pintype "passive"))
      (node (ref "U101") (pin "19") (pinfunction "2B4_19") (pintype "bidirectional"))
    )
    (net (code "138") (name "Net-(U101-2B5)") (class "Default")
      (node (ref "RA104") (pin "7") (pinfunction "7_7") (pintype "passive"))
      (node (ref "U101") (pin "20") (pinfunction "2B5_20") (pintype "bidirectional"))
    )
    (net (code "139") (name "Net-(U101-2B6)") (class "Default")
      (node (ref "RA104") (pin "6") (pinfunction "6_6") (pintype "passive"))
      (node (ref "U101") (pin "22") (pinfunction "2B6_22") (pintype "bidirectional"))
    )
    (net (code "140") (name "Net-(U101-2B7)") (class "Default")
      (node (ref "RA104") (pin "5") (pinfunction "5_5") (pintype "passive"))
      (node (ref "U101") (pin "23") (pinfunction "2B7_23") (pintype "bidirectional"))
    )
    (net (code "141") (name "Net-(U102-1B0)") (class "Default")
      (node (ref "C125") (pin "2") (pinfunction "2_2") (pintype "passive"))
      (node (ref "RA105") (pin "7") (pinfunction "7_7") (pintype "passive"))
      (node (ref "U102") (pin "2") (pinfunction "1B0_2") (pintype "bidirectional"))
    )
    (net (code "142") (name "Net-(U102-1B1)") (class "Default")
      (node (ref "C122") (pin "2") (pinfunction "2_2") (pintype "passive"))
      (node (ref "RA105") (pin "6") (pinfunction "6_6") (pintype "passive"))
      (node (ref "U102") (pin "3") (pinfunction "1B1_3") (pintype "bidirectional"))
    )
    (net (code "143") (name "Net-(U102-1B2)") (class "Default")
      (node (ref "RA105") (pin "5") (pinfunction "5_5") (pintype "passive"))
      (node (ref "U102") (pin "5") (pinfunction "1B2_5") (pintype "bidirectional"))
    )
    (net (code "144") (name "Net-(U102-1B3)") (class "Default")
      (node (ref "RA106") (pin "8") (pinfunction "8_8") (pintype "passive"))
      (node (ref "U102") (pin "6") (pinfunction "1B3_6") (pintype "bidirectional"))
    )
    (net (code "145") (name "Net-(U102-1B4)") (class "Default")
      (node (ref "RA106") (pin "7") (pinfunction "7_7") (pintype "passive"))
      (node (ref "U102") (pin "8") (pinfunction "1B4_8") (pintype "bidirectional"))
    )
    (net (code "146") (name "Net-(U102-1B5)") (class "Default")
      (node (ref "RA106") (pin "6") (pinfunction "6_6") (pintype "passive"))
      (node (ref "U102") (pin "9") (pinfunction "1B5_9") (pintype "bidirectional"))
    )
    (net (code "147") (name "Net-(U102-1B6)") (class "Default")
      (node (ref "RA106") (pin "5") (pinfunction "5_5") (pintype "passive"))
      (node (ref "U102") (pin "11") (pinfunction "1B6_11") (pintype "bidirectional"))
    )
    (net (code "148") (name "Net-(U102-1B7)") (class "Default")
      (node (ref "RA107") (pin "8") (pinfunction "8_8") (pintype "passive"))
      (node (ref "U102") (pin "12") (pinfunction "1B7_12") (pintype "bidirectional"))
    )
    (net (code "149") (name "Net-(U102-2B0)") (class "Default")
      (node (ref "RA107") (pin "7") (pinfunction "7_7") (pintype "passive"))
      (node (ref "U102") (pin "13") (pinfunction "2B0_13") (pintype "bidirectional"))
    )
    (net (code "150") (name "Net-(U102-2B1)") (class "Default")
      (node (ref "RA107") (pin "6") (pinfunction "6_6") (pintype "passive"))
      (node (ref "U102") (pin "14") (pinfunction "2B1_14") (pintype "bidirectional"))
    )
    (net (code "151") (name "Net-(U102-2B2)") (class "Default")
      (node (ref "RA107") (pin "5") (pinfunction "5_5") (pintype "passive"))
      (node (ref "U102") (pin "16") (pinfunction "2B2_16") (pintype "bidirectional"))
    )
    (net (code "152") (name "Net-(U102-2B3)") (class "Default")
      (node (ref "RA108") (pin "8") (pinfunction "8_8") (pintype "passive"))
      (node (ref "U102") (pin "17") (pinfunction "2B3_17") (pintype "bidirectional"))
    )
    (net (code "153") (name "Net-(U102-2B4)") (class "Default")
      (node (ref "RA108") (pin "7") (pinfunction "7_7") (pintype "passive"))
      (node (ref "U102") (pin "19") (pinfunction "2B4_19") (pintype "bidirectional"))
    )
    (net (code "154") (name "Net-(U102-2B5)") (class "Default")
      (node (ref "RA108") (pin "6") (pinfunction "6_6") (pintype "passive"))
      (node (ref "U102") (pin "20") (pinfunction "2B5_20") (pintype "bidirectional"))
    )
    (net (code "155") (name "Net-(U102-2B6)") (class "Default")
      (node (ref "RA108") (pin "5") (pinfunction "5_5") (pintype "passive"))
      (node (ref "U102") (pin "22") (pinfunction "2B6_22") (pintype "bidirectional"))
    )
    (net (code "156") (name "Net-(U102-2B7)") (class "Default")
      (node (ref "RA109") (pin "8") (pinfunction "8_8") (pintype "passive"))
      (node (ref "U102") (pin "23") (pinfunction "2B7_23") (pintype "bidirectional"))
    )
    (net (code "157") (name "Net-(U103-1B0)") (class "Default")
      (node (ref "RA109") (pin "7") (pinfunction "7_7") (pintype "passive"))
      (node (ref "U103") (pin "2") (pinfunction "1B0_2") (pintype "bidirectional"))
    )
    (net (code "158") (name "Net-(U103-1B1)") (class "Default")
      (node (ref "RA109") (pin "6") (pinfunction "6_6") (pintype "passive"))
      (node (ref "U103") (pin "3") (pinfunction "1B1_3") (pintype "bidirectional"))
    )
    (net (code "159") (name "Net-(U103-1B2)") (class "Default")
      (node (ref "RA109") (pin "5") (pinfunction "5_5") (pintype "passive"))
      (node (ref "U103") (pin "5") (pinfunction "1B2_5") (pintype "bidirectional"))
    )
    (net (code "160") (name "Net-(U103-1B3)") (class "Default")
      (node (ref "RA110") (pin "8") (pinfunction "8_8") (pintype "passive"))
      (node (ref "U103") (pin "6") (pinfunction "1B3_6") (pintype "bidirectional"))
    )
    (net (code "161") (name "Net-(U103-1B4)") (class "Default")
      (node (ref "RA110") (pin "7") (pinfunction "7_7") (pintype "passive"))
      (node (ref "U103") (pin "8") (pinfunction "1B4_8") (pintype "bidirectional"))
    )
    (net (code "162") (name "Net-(U103-1B5)") (class "Default")
      (node (ref "RA110") (pin "6") (pinfunction "6_6") (pintype "passive"))
      (node (ref "U103") (pin "9") (pinfunction "1B5_9") (pintype "bidirectional"))
    )
    (net (code "163") (name "Net-(U103-1B6)") (class "Default")
      (node (ref "RA110") (pin "5") (pinfunction "5_5") (pintype "passive"))
      (node (ref "U103") (pin "11") (pinfunction "1B6_11") (pintype "bidirectional"))
    )
    (net (code "164") (name "Net-(U103-1B7)") (class "Default")
      (node (ref "RA111") (pin "8") (pinfunction "8_8") (pintype "passive"))
      (node (ref "U103") (pin "12") (pinfunction "1B7_12") (pintype "bidirectional"))
    )
    (net (code "165") (name "Net-(U103-2B0)") (class "Default")
      (node (ref "RA111") (pin "7") (pinfunction "7_7") (pintype "passive"))
      (node (ref "U103") (pin "13") (pinfunction "2B0_13") (pintype "bidirectional"))
    )
    (net (code "166") (name "Net-(U103-2B1)") (class "Default")
      (node (ref "RA111") (pin "6") (pinfunction "6_6") (pintype "passive"))
      (node (ref "U103") (pin "14") (pinfunction "2B1_14") (pintype "bidirectional"))
    )
    (net (code "167") (name "Net-(U103-2B2)") (class "Default")
      (node (ref "C128") (pin "2") (pinfunction "2_2") (pintype "passive"))
      (node (ref "RA111") (pin "5") (pinfunction "5_5") (pintype "passive"))
      (node (ref "U103") (pin "16") (pinfunction "2B2_16") (pintype "bidirectional"))
    )
    (net (code "168") (name "Net-(U103-2B3)") (class "Default")
      (node (ref "C127") (pin "2") (pinfunction "2_2") (pintype "passive"))
      (node (ref "RA112") (pin "1") (pinfunction "1_1") (pintype "passive"))
      (node (ref "U103") (pin "17") (pinfunction "2B3_17") (pintype "bidirectional"))
    )
    (net (code "169") (name "Net-(U103-2B4)") (class "Default")
      (node (ref "RA112") (pin "2") (pinfunction "2_2") (pintype "passive"))
      (node (ref "U103") (pin "19") (pinfunction "2B4_19") (pintype "bidirectional"))
    )
    (net (code "170") (name "Net-(U103-2B5)") (class "Default")
      (node (ref "RA112") (pin "3") (pinfunction "3_3") (pintype "passive"))
      (node (ref "U103") (pin "20") (pinfunction "2B5_20") (pintype "bidirectional"))
    )
    (net (code "171") (name "Net-(U103-2B6)") (class "Default")
      (node (ref "RA112") (pin "4") (pinfunction "4_4") (pintype "passive"))
      (node (ref "U103") (pin "22") (pinfunction "2B6_22") (pintype "bidirectional"))
    )
    (net (code "172") (name "unconnected-(J101-EXPAND-Pad2)") (class "Default")
      (node (ref "J101") (pin "2") (pinfunction "EXPAND_2") (pintype "passive"))
    )
    (net (code "173") (name "unconnected-(J101-~{WRAM}-Pad32)") (class "Default")
      (node (ref "J101") (pin "32") (pinfunction "~{WRAM}_32") (pintype "passive"))
    )
  )
)
